# Sheet.net
KiCad netlist of a schematic drawn in Altium Designer
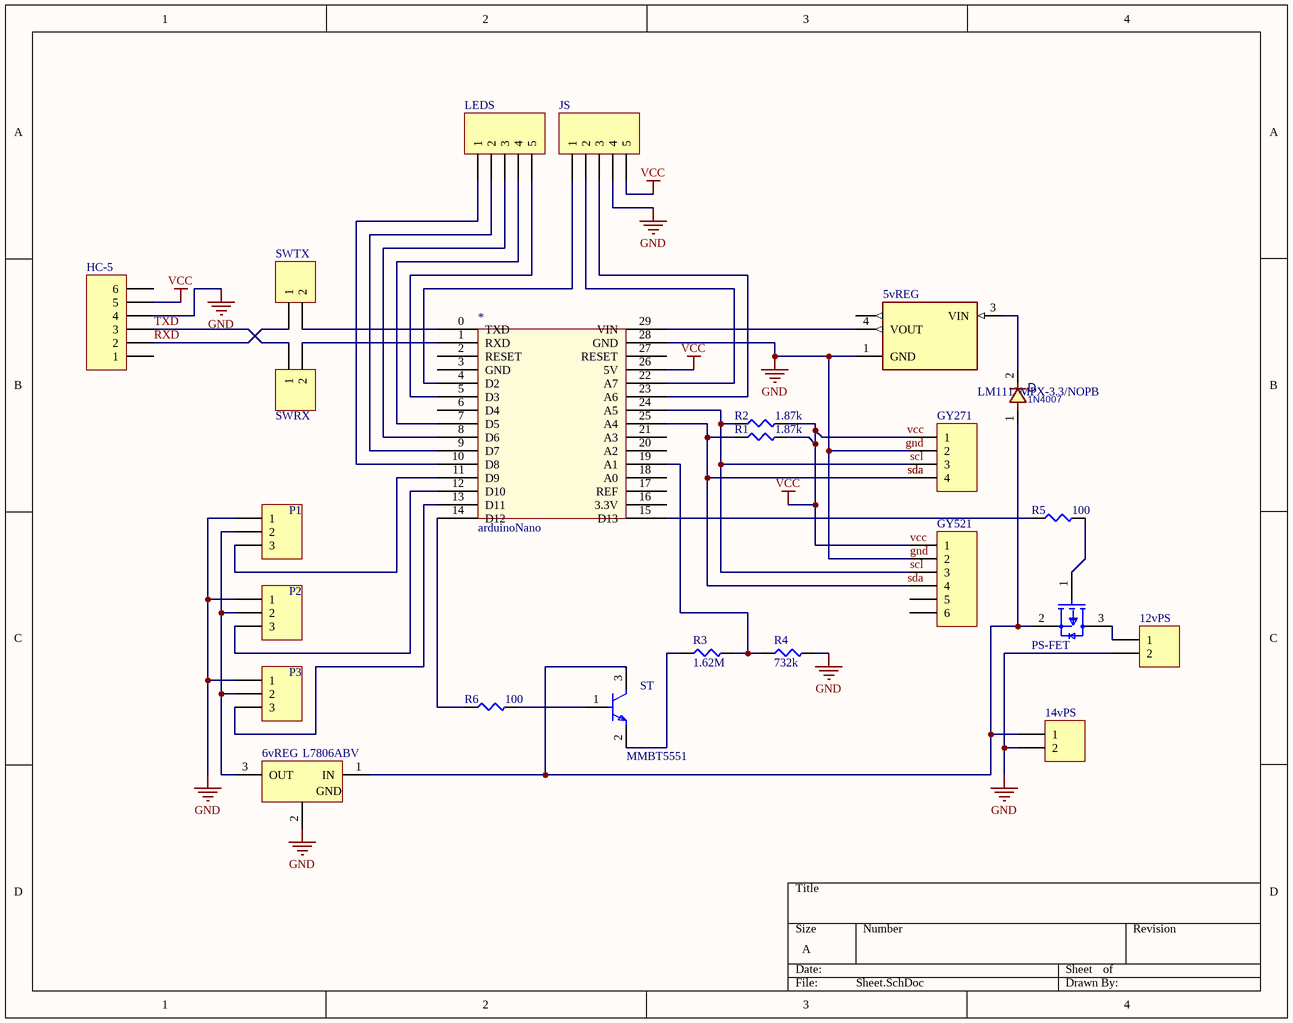
[diagram p0: Sheet.SchDoc]

(export (version "E")
  (design (tool "Eeschema 10.0.6"))
  (components
    (comp (ref "*")
      (value "arduinoNano")
      (footprint "Arduino nano")
      (libsource (lib "nanoArduino") (part "arduinoNano"))
    )
    (comp (ref "5vREG")
      (value "LM1117MPX-3.3-NOPB")
      (footprint "Texas_Instruments_LM1117MPX-3.3-NOPB_0")
      (description "IC REG LINEAR 3.3V 800MA SOT223")
      (fields
        (field (name "PART NUMBER") "LM1117MPX-3.3/NOPB")
        (field (name "DIGIKEY PART NUMBER") "LM1117MPX-3.3/NOPBCT-ND")
      )
      (libsource (lib "EEConcierge(LM1117_3.3)") (part "LM1117MPX-3.3-NOPB"))
    )
    (comp (ref "6vREG")
      (value "L7806ABV")
      (footprint "TO220")
      (description "Positive Voltage Regulator, 6V, 3-Pin TO-220")
      (libsource (lib "STMicroelectronics_L7806ABV") (part "L7806ABV"))
    )
    (comp (ref "12vPS")
      (value "Header 2")
      (footprint "HDR1X2")
      (description "Header, 2-Pin")
      (fields (field (name "PUBLISHER") "Altium Limited"))
      (libsource (lib "") (part "Header 2_2"))
    )
    (comp (ref "14vPS")
      (value "Header 2")
      (footprint "HDR1X2")
      (description "Header, 2-Pin")
      (fields (field (name "PUBLISHER") "Altium Limited"))
      (libsource (lib "") (part "Header 2_2"))
    )
    (comp (ref "D")
      (value "1N4007")
      (footprint "D_SMA")
      (description "DIODE, GENERAL PURPOSE, 1000V/1A")
      (fields (field (name "MANF") "Kingtronics") (field (name "MANF_P#") "M7"))
      (libsource (lib "diode") (part "DIODE_SMD_1N4007"))
    )
    (comp (ref "GY271")
      (value "Header 4")
      (footprint "HDR1X4")
      (description "Header, 4-Pin")
      (fields (field (name "PUBLISHER") "Altium Limited"))
      (libsource (lib "Miscellaneous Connectors") (part "Header 4"))
    )
    (comp (ref "GY521")
      (value "Header 6")
      (footprint "HDR1X6")
      (description "Header, 6-Pin")
      (fields (field (name "PUBLISHER") "Altium Limited"))
      (libsource (lib "") (part "Header 6_1"))
    )
    (comp (ref "HC-5")
      (value "Header 6")
      (footprint "HDR1X6")
      (description "Header, 6-Pin")
      (fields (field (name "PUBLISHER") "Altium Limited"))
      (libsource (lib "Miscellaneous Connectors") (part "Header 6"))
    )
    (comp (ref "JS")
      (value "Header 5")
      (footprint "HDR1X5")
      (description "Header, 5-Pin")
      (fields (field (name "PUBLISHER") "Altium Limited"))
      (libsource (lib "Miscellaneous Connectors") (part "Header 5"))
    )
    (comp (ref "LEDS")
      (value "Header 5")
      (footprint "HDR1X5")
      (description "Header, 5-Pin")
      (fields (field (name "PUBLISHER") "Altium Limited"))
      (libsource (lib "Miscellaneous Connectors") (part "Header 5"))
    )
    (comp (ref "P1")
      (value "Header 3")
      (footprint "HDR1X3")
      (description "Header, 3-Pin")
      (fields (field (name "PUBLISHER") "Altium Limited"))
      (libsource (lib "Miscellaneous Connectors") (part "Header 3"))
    )
    (comp (ref "P2")
      (value "Header 3")
      (footprint "HDR1X3")
      (description "Header, 3-Pin")
      (fields (field (name "PUBLISHER") "Altium Limited"))
      (libsource (lib "Miscellaneous Connectors") (part "Header 3"))
    )
    (comp (ref "P3")
      (value "Header 3")
      (footprint "HDR1X3")
      (description "Header, 3-Pin")
      (fields (field (name "PUBLISHER") "Altium Limited"))
      (libsource (lib "Miscellaneous Connectors") (part "Header 3"))
    )
    (comp (ref "PS-FET")
      (value "SI2301BDS-T1-E3")
      (footprint "Vishay_Siliconix_S-03946_MFG")
      (description "TRANS MOSFET P-CH 20V 2.2A SOT23-3")
      (fields
        (field (name "DIGIKEY PART NUMBER") "SI2301BDS-T1-E3CT-ND")
        (field (name "MANUFACTURER") "Vishay Siliconix")
      )
      (libsource (lib "EEConcierge") (part "SI2301BDS-T1-E3"))
    )
    (comp (ref "R1")
      (value "1.87k")
      (footprint "SMD-1206-RES")
      (description "RES SMD 1.87K OHM 1% 1/4W 1206")
      (fields
        (field (name "PART NUMBER") "ERJ-8ENF1871V")
        (field (name "DIGI-KEY PART NUMBER") "P1.87KFCT-ND")
      )
      (libsource (lib "Panasonic_ERJ_1206") (part "ERJ-8ENF1871V"))
    )
    (comp (ref "R2")
      (value "1.87k")
      (footprint "SMD-1206-RES")
      (description "RES SMD 1.87K OHM 1% 1/4W 1206")
      (fields
        (field (name "PART NUMBER") "ERJ-8ENF1871V")
        (field (name "DIGI-KEY PART NUMBER") "P1.87KFCT-ND")
      )
      (libsource (lib "Panasonic_ERJ_1206") (part "ERJ-8ENF1871V"))
    )
    (comp (ref "R3")
      (value "1.62M")
      (footprint "SMD-1206-RES")
      (description "RES SMD 1.62K OHM 1% 1/4W 1206")
      (fields
        (field (name "PART NUMBER") "ERJ-8ENF1621V")
        (field (name "DIGI-KEY PART NUMBER") "P1.62KFCT-ND")
      )
      (libsource (lib "Panasonic_ERJ_1206") (part "ERJ-8ENF1621V"))
    )
    (comp (ref "R4")
      (value "732k")
      (footprint "SMD-1206-RES")
      (description "RES SMD 732K OHM 1% 1/4W 1206")
      (fields
        (field (name "PART NUMBER") "ERJ-8ENF7323V")
        (field (name "DIGI-KEY PART NUMBER") "P732KFCT-ND")
      )
      (libsource (lib "Panasonic_ERJ_1206") (part "ERJ-8ENF7323V"))
    )
    (comp (ref "R5")
      (value "100")
      (footprint "SMD-1206-RES")
      (description "RES SMD 100 OHM 1% 1/4W 1206")
      (fields (field (name "PART NUMBER") "ERJ-8ENF1000V") (field (name "DIGI-KEY PART NUMBER") "P100FCT-ND"))
      (libsource (lib "Panasonic_ERJ_1206") (part "ERJ-8ENF1000V"))
    )
    (comp (ref "R6")
      (value "100")
      (footprint "SMD-1206-RES")
      (description "RES SMD 100 OHM 1% 1/4W 1206")
      (fields (field (name "PART NUMBER") "ERJ-8ENF1000V") (field (name "DIGI-KEY PART NUMBER") "P100FCT-ND"))
      (libsource (lib "Panasonic_ERJ_1206") (part "ERJ-8ENF1000V"))
    )
    (comp (ref "ST")
      (value "MMBT5551")
      (footprint "ON_Semi_318BM_0")
      (description "TRANS NPN 160V 0.6A SOT-23")
      (fields (field (name "DIGIKEY PART NUMBER") "MMBT5551FSCT-ND") (field (name "MANUFACTURER") "ON Semi"))
      (libsource (lib "EEConcierge") (part "MMBT5551"))
    )
    (comp (ref "SWRX")
      (value "Header 2")
      (footprint "HDR1X2")
      (description "Header, 2-Pin")
      (fields (field (name "PUBLISHER") "Altium Limited"))
      (libsource (lib "Miscellaneous Connectors") (part "Header 2"))
    )
    (comp (ref "SWTX")
      (value "Header 2")
      (footprint "HDR1X2")
      (description "Header, 2-Pin")
      (fields (field (name "PUBLISHER") "Altium Limited"))
      (libsource (lib "") (part "Header 2_1"))
    )
  )
  (nets
    (net (code "1") (name "/RXD") (class "Default")
      (node (ref "HC-5") (pin "2") (pinfunction "2_2") (pintype "passive"))
      (node (ref "SWTX") (pin "1") (pinfunction "1_1") (pintype "passive"))
    )
    (net (code "2") (name "/TXD") (class "Default")
      (node (ref "HC-5") (pin "3") (pinfunction "3_3") (pintype "passive"))
      (node (ref "SWRX") (pin "1") (pinfunction "1_1") (pintype "passive"))
    )
    (net (code "3") (name "/scl") (class "Default")
      (node (ref "*") (pin "24") (pinfunction "A5_24") (pintype "passive"))
      (node (ref "GY271") (pin "3") (pinfunction "3_3") (pintype "passive"))
      (node (ref "GY521") (pin "3") (pinfunction "3_3") (pintype "passive"))
      (node (ref "R2") (pin "1") (pinfunction "1_1") (pintype "passive"))
    )
    (net (code "4") (name "/sda") (class "Default")
      (node (ref "*") (pin "25") (pinfunction "A4_25") (pintype "passive"))
      (node (ref "GY271") (pin "4") (pinfunction "4_4") (pintype "passive"))
      (node (ref "GY521") (pin "4") (pinfunction "4_4") (pintype "passive"))
      (node (ref "R1") (pin "1") (pinfunction "1_1") (pintype "passive"))
    )
    (net (code "5") (name "GND") (class "Default")
      (node (ref "*") (pin "28") (pinfunction "GND_28") (pintype "passive"))
      (node (ref "12vPS") (pin "2") (pinfunction "2_2") (pintype "passive"))
      (node (ref "14vPS") (pin "2") (pinfunction "2_2") (pintype "passive"))
      (node (ref "5vREG") (pin "1") (pinfunction "GND_1") (pintype "power_in"))
      (node (ref "6vREG") (pin "2") (pinfunction "GND_2") (pintype "power_in"))
      (node (ref "GY271") (pin "2") (pinfunction "2_2") (pintype "passive"))
      (node (ref "GY521") (pin "2") (pinfunction "2_2") (pintype "passive"))
      (node (ref "HC-5") (pin "4") (pinfunction "4_4") (pintype "passive"))
      (node (ref "JS") (pin "4") (pinfunction "4_4") (pintype "passive"))
      (node (ref "P1") (pin "1") (pinfunction "1_1") (pintype "passive"))
      (node (ref "P2") (pin "1") (pinfunction "1_1") (pintype "passive"))
      (node (ref "P3") (pin "1") (pinfunction "1_1") (pintype "passive"))
      (node (ref "R4") (pin "2") (pinfunction "2_2") (pintype "passive"))
    )
    (net (code "6") (name "Net-(*-A1)") (class "Default")
      (node (ref "*") (pin "19") (pinfunction "A1_19") (pintype "passive"))
      (node (ref "R3") (pin "2") (pinfunction "2_2") (pintype "passive"))
      (node (ref "R4") (pin "1") (pinfunction "1_1") (pintype "passive"))
    )
    (net (code "7") (name "Net-(*-A6)") (class "Default")
      (node (ref "*") (pin "23") (pinfunction "A6_23") (pintype "passive"))
      (node (ref "JS") (pin "3") (pinfunction "3_3") (pintype "passive"))
    )
    (net (code "8") (name "Net-(*-A7)") (class "Default")
      (node (ref "*") (pin "22") (pinfunction "A7_22") (pintype "passive"))
      (node (ref "JS") (pin "2") (pinfunction "2_2") (pintype "passive"))
    )
    (net (code "9") (name "Net-(*-D2)") (class "Default")
      (node (ref "*") (pin "4") (pinfunction "D2_4") (pintype "passive"))
      (node (ref "JS") (pin "1") (pinfunction "1_1") (pintype "passive"))
    )
    (net (code "10") (name "Net-(*-D3)") (class "Default")
      (node (ref "*") (pin "5") (pinfunction "D3_5") (pintype "passive"))
      (node (ref "LEDS") (pin "5") (pinfunction "5_5") (pintype "passive"))
    )
    (net (code "11") (name "Net-(*-D5)") (class "Default")
      (node (ref "*") (pin "7") (pinfunction "D5_7") (pintype "passive"))
      (node (ref "LEDS") (pin "4") (pinfunction "4_4") (pintype "passive"))
    )
    (net (code "12") (name "Net-(*-D6)") (class "Default")
      (node (ref "*") (pin "8") (pinfunction "D6_8") (pintype "passive"))
      (node (ref "LEDS") (pin "3") (pinfunction "3_3") (pintype "passive"))
    )
    (net (code "13") (name "Net-(*-D7)") (class "Default")
      (node (ref "*") (pin "9") (pinfunction "D7_9") (pintype "passive"))
      (node (ref "LEDS") (pin "2") (pinfunction "2_2") (pintype "passive"))
    )
    (net (code "14") (name "Net-(*-D8)") (class "Default")
      (node (ref "*") (pin "10") (pinfunction "D8_10") (pintype "passive"))
      (node (ref "LEDS") (pin "1") (pinfunction "1_1") (pintype "passive"))
    )
    (net (code "15") (name "Net-(*-D9)") (class "Default")
      (node (ref "*") (pin "11") (pinfunction "D9_11") (pintype "passive"))
      (node (ref "P1") (pin "3") (pinfunction "3_3") (pintype "passive"))
    )
    (net (code "16") (name "Net-(*-D10)") (class "Default")
      (node (ref "*") (pin "12") (pinfunction "D10_12") (pintype "passive"))
      (node (ref "P2") (pin "3") (pinfunction "3_3") (pintype "passive"))
    )
    (net (code "17") (name "Net-(*-D11)") (class "Default")
      (node (ref "*") (pin "13") (pinfunction "D11_13") (pintype "passive"))
      (node (ref "P3") (pin "3") (pinfunction "3_3") (pintype "passive"))
    )
    (net (code "18") (name "Net-(*-D12)") (class "Default")
      (node (ref "*") (pin "14") (pinfunction "D12_14") (pintype "passive"))
      (node (ref "R6") (pin "1") (pinfunction "1_1") (pintype "passive"))
    )
    (net (code "19") (name "Net-(*-D13)") (class "Default")
      (node (ref "*") (pin "15") (pinfunction "D13_15") (pintype "passive"))
      (node (ref "R5") (pin "1") (pinfunction "1_1") (pintype "passive"))
    )
    (net (code "20") (name "Net-(*-RXD)") (class "Default")
      (node (ref "*") (pin "1") (pinfunction "RXD_1") (pintype "passive"))
      (node (ref "SWRX") (pin "2") (pinfunction "2_2") (pintype "passive"))
    )
    (net (code "21") (name "Net-(*-TXD)") (class "Default")
      (node (ref "*") (pin "0") (pinfunction "TXD_0") (pintype "passive"))
      (node (ref "SWTX") (pin "2") (pinfunction "2_2") (pintype "passive"))
    )
    (net (code "22") (name "Net-(*-VIN)") (class "Default")
      (node (ref "*") (pin "29") (pinfunction "VIN_29") (pintype "passive"))
      (node (ref "5vREG") (pin "4") (pinfunction "VOUT_4") (pintype "output"))
    )
    (net (code "23") (name "Net-(5vREG-VIN)") (class "Default")
      (node (ref "5vREG") (pin "3") (pinfunction "VIN_3") (pintype "input"))
      (node (ref "D") (pin "2") (pinfunction "2_2") (pintype "passive"))
    )
    (net (code "24") (name "Net-(6vREG-IN)") (class "Default")
      (node (ref "14vPS") (pin "1") (pinfunction "1_1") (pintype "passive"))
      (node (ref "6vREG") (pin "1") (pinfunction "IN_1") (pintype "power_in"))
      (node (ref "D") (pin "1") (pinfunction "1_1") (pintype "passive"))
      (node (ref "PS-FET") (pin "2") (pinfunction "S_2") (pintype "passive"))
      (node (ref "ST") (pin "3") (pinfunction "C_3") (pintype "passive"))
    )
    (net (code "25") (name "Net-(6vREG-OUT)") (class "Default")
      (node (ref "6vREG") (pin "3") (pinfunction "OUT_3") (pintype "power_in"))
      (node (ref "P1") (pin "2") (pinfunction "2_2") (pintype "passive"))
      (node (ref "P2") (pin "2") (pinfunction "2_2") (pintype "passive"))
      (node (ref "P3") (pin "2") (pinfunction "2_2") (pintype "passive"))
    )
    (net (code "26") (name "Net-(PS-FET-D)") (class "Default")
      (node (ref "12vPS") (pin "1") (pinfunction "1_1") (pintype "passive"))
      (node (ref "PS-FET") (pin "3") (pinfunction "D_3") (pintype "passive"))
    )
    (net (code "27") (name "Net-(PS-FET-G)") (class "Default")
      (node (ref "PS-FET") (pin "1") (pinfunction "G_1") (pintype "passive"))
      (node (ref "R5") (pin "2") (pinfunction "2_2") (pintype "passive"))
    )
    (net (code "28") (name "Net-(ST-B)") (class "Default")
      (node (ref "R6") (pin "2") (pinfunction "2_2") (pintype "passive"))
      (node (ref "ST") (pin "1") (pinfunction "B_1") (pintype "passive"))
    )
    (net (code "29") (name "Net-(ST-E)") (class "Default")
      (node (ref "R3") (pin "1") (pinfunction "1_1") (pintype "passive"))
      (node (ref "ST") (pin "2") (pinfunction "E_2") (pintype "passive"))
    )
    (net (code "30") (name "VCC") (class "Default")
      (node (ref "*") (pin "26") (pinfunction "5V_26") (pintype "passive"))
      (node (ref "GY271") (pin "1") (pinfunction "1_1") (pintype "passive"))
      (node (ref "GY521") (pin "1") (pinfunction "1_1") (pintype "passive"))
      (node (ref "HC-5") (pin "5") (pinfunction "5_5") (pintype "passive"))
      (node (ref "JS") (pin "5") (pinfunction "5_5") (pintype "passive"))
      (node (ref "R1") (pin "2") (pinfunction "2_2") (pintype "passive"))
      (node (ref "R2") (pin "2") (pinfunction "2_2") (pintype "passive"))
    )
    (net (code "31") (name "unconnected-(*-3.3V-Pad16)") (class "Default")
      (node (ref "*") (pin "16") (pinfunction "3.3V_16") (pintype "passive"))
    )
    (net (code "32") (name "unconnected-(*-A0-Pad18)") (class "Default")
      (node (ref "*") (pin "18") (pinfunction "A0_18") (pintype "passive"))
    )
    (net (code "33") (name "unconnected-(*-A2-Pad20)") (class "Default")
      (node (ref "*") (pin "20") (pinfunction "A2_20") (pintype "passive"))
    )
    (net (code "34") (name "unconnected-(*-A3-Pad21)") (class "Default")
      (node (ref "*") (pin "21") (pinfunction "A3_21") (pintype "passive"))
    )
    (net (code "35") (name "unconnected-(*-D4-Pad6)") (class "Default")
      (node (ref "*") (pin "6") (pinfunction "D4_6") (pintype "passive"))
    )
    (net (code "36") (name "unconnected-(*-GND-Pad3)") (class "Default")
      (node (ref "*") (pin "3") (pinfunction "GND_3") (pintype "passive"))
    )
    (net (code "37") (name "unconnected-(*-REF-Pad17)") (class "Default")
      (node (ref "*") (pin "17") (pinfunction "REF_17") (pintype "passive"))
    )
    (net (code "38") (name "unconnected-(*-RESET-Pad2)") (class "Default")
      (node (ref "*") (pin "2") (pinfunction "RESET_2") (pintype "passive"))
    )
    (net (code "39") (name "unconnected-(*-RESET-Pad27)") (class "Default")
      (node (ref "*") (pin "27") (pinfunction "RESET_27") (pintype "passive"))
    )
    (net (code "40") (name "unconnected-(5vREG-VOUT-Pad2)") (class "Default")
      (node (ref "5vREG") (pin "2") (pinfunction "VOUT_2") (pintype "output"))
    )
    (net (code "41") (name "unconnected-(GY521-Pad5)") (class "Default")
      (node (ref "GY521") (pin "5") (pinfunction "5_5") (pintype "passive"))
    )
    (net (code "42") (name "unconnected-(GY521-Pad6)") (class "Default")
      (node (ref "GY521") (pin "6") (pinfunction "6_6") (pintype "passive"))
    )
    (net (code "43") (name "unconnected-(HC-5-Pad1)") (class "Default")
      (node (ref "HC-5") (pin "1") (pinfunction "1_1") (pintype "passive"))
    )
    (net (code "44") (name "unconnected-(HC-5-Pad6)") (class "Default")
      (node (ref "HC-5") (pin "6") (pinfunction "6_6") (pintype "passive"))
    )
  )
)
